# Sheet1.net
KiCad netlist of a schematic drawn in Altium Designer
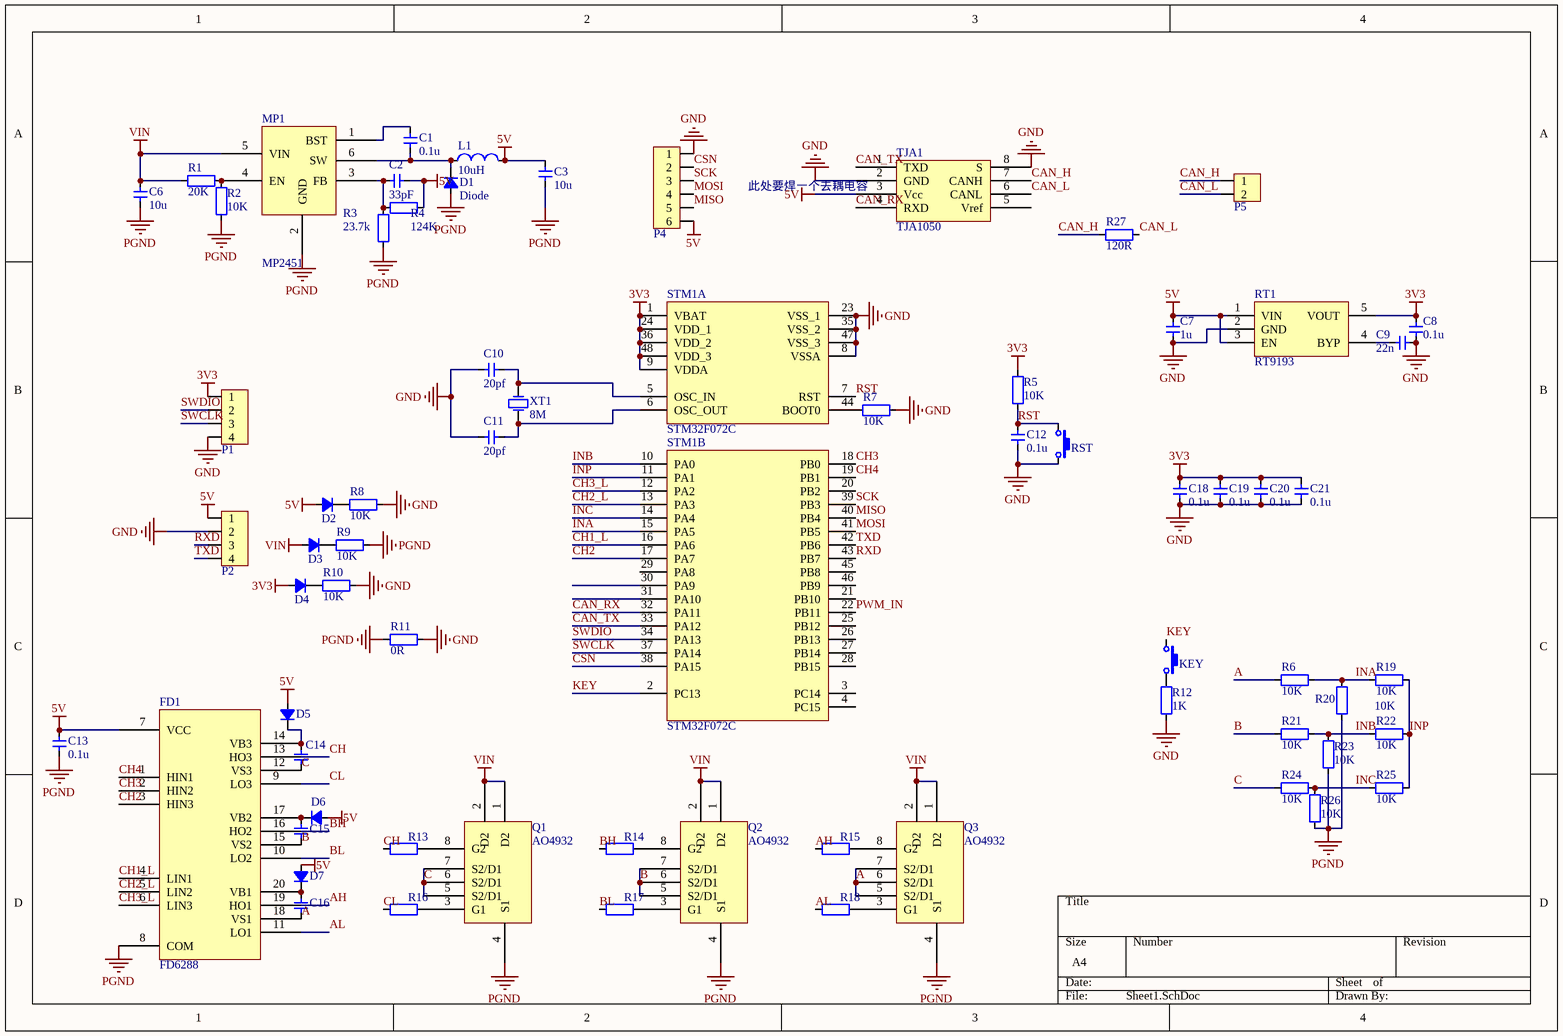
[diagram p0: Sheet1.SchDoc]

(export (version "E")
  (design (tool "Eeschema 10.0.6"))
  (components
    (comp (ref "C1")
      (value "0.1u")
      (footprint "PCB_PassiveCap:CAP_0603")
      (description "Capacitor")
      (fields (field (name "Comment") "Cap_0603"))
      (libsource (lib "SCH_Passive") (part "Cap_0603"))
    )
    (comp (ref "C2")
      (value "33pF")
      (footprint "PCB_PassiveCap:CAP_0603")
      (description "Capacitor")
      (fields (field (name "Comment") "Cap_0603"))
      (libsource (lib "SCH_Passive") (part "Cap_0603"))
    )
    (comp (ref "C3")
      (value "10u")
      (footprint "PCB_PassiveCap:CAP_0805")
      (description "Capacitor")
      (fields (field (name "Comment") "Cap_0805"))
      (libsource (lib "SCH_Passive") (part "Cap_0805"))
    )
    (comp (ref "C6")
      (value "10u")
      (footprint "PCB_PassiveCap:CAP_0805")
      (description "Capacitor")
      (fields (field (name "Comment") "Cap_0805"))
      (libsource (lib "SCH_Passive") (part "Cap_0805"))
    )
    (comp (ref "C7")
      (value "1u")
      (footprint "PCB_PassiveCap:CAP_0603")
      (description "Capacitor")
      (fields (field (name "Comment") "Cap_0603"))
      (libsource (lib "SCH_Passive") (part "Cap_0603"))
    )
    (comp (ref "C8")
      (value "0.1u")
      (footprint "PCB_PassiveCap:CAP_0603")
      (description "Capacitor")
      (fields (field (name "Comment") "Cap_0603"))
      (libsource (lib "SCH_Passive") (part "Cap_0603"))
    )
    (comp (ref "C9")
      (value "22n")
      (footprint "PCB_PassiveCap:CAP_0603")
      (description "Capacitor")
      (fields (field (name "Comment") "Cap_0603"))
      (libsource (lib "SCH_Passive") (part "Cap_0603"))
    )
    (comp (ref "C10")
      (value "20pf")
      (footprint "PCB_PassiveCap:CAP_0603")
      (description "Capacitor")
      (fields (field (name "Comment") "Cap_0603"))
      (libsource (lib "SCH_Passive") (part "Cap_0603"))
    )
    (comp (ref "C11")
      (value "20pf")
      (footprint "PCB_PassiveCap:CAP_0603")
      (description "Capacitor")
      (fields (field (name "Comment") "Cap_0603"))
      (libsource (lib "SCH_Passive") (part "Cap_0603"))
    )
    (comp (ref "C12")
      (value "0.1u")
      (footprint "PCB_PassiveCap:CAP_0603")
      (description "Capacitor")
      (fields (field (name "Comment") "Cap_0603"))
      (libsource (lib "SCH_Passive") (part "Cap_0603"))
    )
    (comp (ref "C13")
      (value "0.1u")
      (footprint "PCB_PassiveCap:CAP_0603")
      (description "Capacitor")
      (fields (field (name "Comment") "Cap_0603"))
      (libsource (lib "SCH_Passive") (part "Cap_0603"))
    )
    (comp (ref "C14")
      (value "Cap_0603")
      (footprint "PCB_PassiveCap:CAP_0603")
      (description "Capacitor")
      (libsource (lib "SCH_Passive") (part "Cap_0603"))
    )
    (comp (ref "C15")
      (value "Cap_0603")
      (footprint "PCB_PassiveCap:CAP_0603")
      (description "Capacitor")
      (libsource (lib "SCH_Passive") (part "Cap_0603"))
    )
    (comp (ref "C16")
      (value "Cap_0603")
      (footprint "PCB_PassiveCap:CAP_0603")
      (description "Capacitor")
      (libsource (lib "SCH_Passive") (part "Cap_0603"))
    )
    (comp (ref "C18")
      (value "0.1u")
      (footprint "PCB_PassiveCap:CAP_0603")
      (description "Capacitor")
      (fields (field (name "Comment") "Cap_0603"))
      (libsource (lib "SCH_Passive") (part "Cap_0603"))
    )
    (comp (ref "C19")
      (value "0.1u")
      (footprint "PCB_PassiveCap:CAP_0603")
      (description "Capacitor")
      (fields (field (name "Comment") "Cap_0603"))
      (libsource (lib "SCH_Passive") (part "Cap_0603"))
    )
    (comp (ref "C20")
      (value "0.1u")
      (footprint "PCB_PassiveCap:CAP_0603")
      (description "Capacitor")
      (fields (field (name "Comment") "Cap_0603"))
      (libsource (lib "SCH_Passive") (part "Cap_0603"))
    )
    (comp (ref "C21")
      (value "0.1u")
      (footprint "PCB_PassiveCap:CAP_0603")
      (description "Capacitor")
      (fields (field (name "Comment") "Cap_0603"))
      (libsource (lib "SCH_Passive") (part "Cap_0603"))
    )
    (comp (ref "D1") (value "Diode") (footprint "LED_0805_RED") (libsource (lib "SCH_Active") (part "Diode")))
    (comp (ref "D2")
      (value "D_0805")
      (footprint "LED_0805_YELLOW")
      (libsource (lib "SCH_Active") (part "D_0805"))
    )
    (comp (ref "D3")
      (value "D_0805")
      (footprint "LED_0805_YELLOW")
      (libsource (lib "SCH_Active") (part "D_0805"))
    )
    (comp (ref "D4")
      (value "D_0805")
      (footprint "LED_0805_YELLOW")
      (libsource (lib "SCH_Active") (part "D_0805"))
    )
    (comp (ref "D5")
      (value "D_0805")
      (footprint "LED_0805_YELLOW")
      (libsource (lib "SCH_Active") (part "D_0805"))
    )
    (comp (ref "D6")
      (value "D_0805")
      (footprint "LED_0805_YELLOW")
      (libsource (lib "SCH_Active") (part "D_0805"))
    )
    (comp (ref "D7")
      (value "D_0805")
      (footprint "LED_0805_YELLOW")
      (libsource (lib "SCH_Active") (part "D_0805"))
    )
    (comp (ref "FD1")
      (value "FD6288")
      (footprint "TSSOP_E170_P0.65_20")
      (libsource (lib "SCH_IntegratedCircuit") (part "FD6288"))
    )
    (comp (ref "KEY")
      (value "ButtonTACT_3x4x2_180")
      (footprint "PCB_Switch:ButtonTACT_3x4x2_180H")
      (description "Button")
      (libsource (lib "SCH_Switch") (part "ButtonTACT_3x4x2_180"))
    )
    (comp (ref "L1")
      (value "10uH")
      (footprint "IND_CD52")
      (description "Inductor")
      (fields (field (name "Comment") "Ind_CD32"))
      (libsource (lib "SCH_Passive") (part "Ind_CD32"))
    )
    (comp (ref "MP1")
      (value "MP2451")
      (footprint "SOT23-6")
      (libsource (lib "SCH_IntegratedCircuit") (part "MP2451"))
    )
    (comp (ref "P1")
      (value "HDR1x4_2.54")
      (footprint "PCB_ConnectorHDR:HDR1x4_2.54_180")
      (description "Header")
      (libsource (lib "SCH_ConnectorHDR") (part "HDR1x4_2.54"))
    )
    (comp (ref "P2")
      (value "HDR1x4_2.54")
      (footprint "PCB_ConnectorHDR:HDR1x4_2.54_180")
      (description "Header")
      (libsource (lib "SCH_ConnectorHDR") (part "HDR1x4_2.54"))
    )
    (comp (ref "P4")
      (value "HDR1x6_2.54")
      (footprint "PCB_ConnectorHDR:1.25mm_1X6_SMT")
      (description "Header")
      (libsource (lib "SCH_ConnectorHDR") (part "HDR1x6_2.54T"))
    )
    (comp (ref "P5")
      (value "HDR1x2_2.54")
      (footprint "PCB_ConnectorHDR:HDR1X2_2.54_180")
      (description "Header")
      (libsource (lib "SCH_ConnectorHDR") (part "HDR1x2_2.54"))
    )
    (comp (ref "Q1") (value "AO4932") (footprint "SOP_E150_8") (libsource (lib "SCH_Active") (part "AO4932")))
    (comp (ref "Q2") (value "AO4932") (footprint "SOP_E150_8") (libsource (lib "SCH_Active") (part "AO4932")))
    (comp (ref "Q3") (value "AO4932") (footprint "SOP_E150_8") (libsource (lib "SCH_Active") (part "AO4932")))
    (comp (ref "R1")
      (value "20K")
      (footprint "PCB_PassiveRes:RES_0603")
      (description "Resistor")
      (fields (field (name "Comment") "Res_0603"))
      (libsource (lib "") (part "Res_0603_1"))
    )
    (comp (ref "R2")
      (value "10K")
      (footprint "PCB_PassiveRes:RES_0603")
      (description "Resistor")
      (fields (field (name "Comment") "Res_0603"))
      (libsource (lib "") (part "Res_0603_3"))
    )
    (comp (ref "R3")
      (value "23.7k")
      (footprint "PCB_PassiveRes:RES_0603")
      (description "Resistor")
      (fields (field (name "Comment") "Res_0603"))
      (libsource (lib "") (part "Res_0603_3"))
    )
    (comp (ref "R4")
      (value "124K")
      (footprint "PCB_PassiveRes:RES_0603")
      (description "Resistor")
      (fields (field (name "Comment") "Res_0603"))
      (libsource (lib "") (part "Res_0603_1"))
    )
    (comp (ref "R5")
      (value "10K")
      (footprint "PCB_PassiveRes:RES_0603")
      (description "Resistor")
      (fields (field (name "Comment") "Res_0603"))
      (libsource (lib "SCH_Passive") (part "Res_0603"))
    )
    (comp (ref "R6")
      (value "10K")
      (footprint "PCB_PassiveRes:RES_0603")
      (description "Resistor")
      (fields (field (name "Comment") "Res_0603"))
      (libsource (lib "") (part "Res_0603_1"))
    )
    (comp (ref "R7")
      (value "10K")
      (footprint "PCB_PassiveRes:RES_0603")
      (description "Resistor")
      (fields (field (name "Comment") "Res_0603"))
      (libsource (lib "") (part "Res_0603_2"))
    )
    (comp (ref "R8")
      (value "10K")
      (footprint "PCB_PassiveRes:RES_0603")
      (description "Resistor")
      (fields (field (name "Comment") "Res_0603"))
      (libsource (lib "") (part "Res_0603_1"))
    )
    (comp (ref "R9")
      (value "10K")
      (footprint "PCB_PassiveRes:RES_0603")
      (description "Resistor")
      (fields (field (name "Comment") "Res_0603"))
      (libsource (lib "") (part "Res_0603_1"))
    )
    (comp (ref "R10")
      (value "10K")
      (footprint "PCB_PassiveRes:RES_0603")
      (description "Resistor")
      (fields (field (name "Comment") "Res_0603"))
      (libsource (lib "") (part "Res_0603_1"))
    )
    (comp (ref "R11")
      (value "0R")
      (footprint "PCB_PassiveRes:RES_0603")
      (description "Resistor")
      (fields (field (name "Comment") "Res_0603"))
      (libsource (lib "") (part "Res_0603_1"))
    )
    (comp (ref "R12")
      (value "1K")
      (footprint "PCB_PassiveRes:RES_0603")
      (description "Resistor")
      (fields (field (name "Comment") "Res_0603"))
      (libsource (lib "SCH_Passive") (part "Res_0603"))
    )
    (comp (ref "R13")
      (value "Res_0603")
      (footprint "PCB_PassiveRes:RES_0603")
      (description "Resistor")
      (libsource (lib "") (part "Res_0603_1"))
    )
    (comp (ref "R14")
      (value "Res_0603")
      (footprint "PCB_PassiveRes:RES_0603")
      (description "Resistor")
      (libsource (lib "") (part "Res_0603_1"))
    )
    (comp (ref "R15")
      (value "Res_0603")
      (footprint "PCB_PassiveRes:RES_0603")
      (description "Resistor")
      (libsource (lib "") (part "Res_0603_1"))
    )
    (comp (ref "R16")
      (value "Res_0603")
      (footprint "PCB_PassiveRes:RES_0603")
      (description "Resistor")
      (libsource (lib "") (part "Res_0603_1"))
    )
    (comp (ref "R17")
      (value "Res_0603")
      (footprint "PCB_PassiveRes:RES_0603")
      (description "Resistor")
      (libsource (lib "") (part "Res_0603_1"))
    )
    (comp (ref "R18")
      (value "Res_0603")
      (footprint "PCB_PassiveRes:RES_0603")
      (description "Resistor")
      (libsource (lib "") (part "Res_0603_1"))
    )
    (comp (ref "R19")
      (value "10K")
      (footprint "PCB_PassiveRes:RES_0603")
      (description "Resistor")
      (fields (field (name "Comment") "Res_0603"))
      (libsource (lib "") (part "Res_0603_1"))
    )
    (comp (ref "R20")
      (value "10K")
      (footprint "PCB_PassiveRes:RES_0603")
      (description "Resistor")
      (fields (field (name "Comment") "Res_0603"))
      (libsource (lib "SCH_Passive") (part "Res_0603"))
    )
    (comp (ref "R21")
      (value "10K")
      (footprint "PCB_PassiveRes:RES_0603")
      (description "Resistor")
      (fields (field (name "Comment") "Res_0603"))
      (libsource (lib "") (part "Res_0603_1"))
    )
    (comp (ref "R22")
      (value "10K")
      (footprint "PCB_PassiveRes:RES_0603")
      (description "Resistor")
      (fields (field (name "Comment") "Res_0603"))
      (libsource (lib "") (part "Res_0603_1"))
    )
    (comp (ref "R23")
      (value "10K")
      (footprint "PCB_PassiveRes:RES_0603")
      (description "Resistor")
      (fields (field (name "Comment") "Res_0603"))
      (libsource (lib "SCH_Passive") (part "Res_0603"))
    )
    (comp (ref "R24")
      (value "10K")
      (footprint "PCB_PassiveRes:RES_0603")
      (description "Resistor")
      (fields (field (name "Comment") "Res_0603"))
      (libsource (lib "") (part "Res_0603_1"))
    )
    (comp (ref "R25")
      (value "10K")
      (footprint "PCB_PassiveRes:RES_0603")
      (description "Resistor")
      (fields (field (name "Comment") "Res_0603"))
      (libsource (lib "") (part "Res_0603_1"))
    )
    (comp (ref "R26")
      (value "10K")
      (footprint "PCB_PassiveRes:RES_0603")
      (description "Resistor")
      (fields (field (name "Comment") "Res_0603"))
      (libsource (lib "SCH_Passive") (part "Res_0603"))
    )
    (comp (ref "R27")
      (value "120R")
      (footprint "PCB_PassiveRes:RES_0603")
      (description "Resistor")
      (fields (field (name "Comment") "Res_0603"))
      (libsource (lib "") (part "Res_0603_2"))
    )
    (comp (ref "RST")
      (value "ButtonTACT_3x4x2_180")
      (footprint "PCB_Switch:ButtonTACT_3x4x2_180H")
      (description "Button")
      (libsource (lib "SCH_Switch") (part "ButtonTACT_3x4x2_180"))
    )
    (comp (ref "RT1")
      (value "RT9193")
      (footprint "PCB_IntegratedCircuit:SOT23-5")
      (description "Power")
      (libsource (lib "SCH_IntegratedCircuit") (part "RT9193"))
    )
    (comp (ref "STM1")
      (value "STM32F072C")
      (footprint "PCB_IntegratedCircuit:LQFP_P0.5_48")
      (description "MCU")
      (libsource (lib "SCH_IntegratedCircuit") (part "STM32F103C"))
    )
    (comp (ref "TJA1")
      (value "TJA1050")
      (footprint "SOP_E150_8")
      (libsource (lib "SCH_IntegratedCircuit") (part "TJA1050"))
    )
    (comp (ref "XT1")
      (value "8M")
      (footprint "PCB_Oscillator:XT_5032_2")
      (description "Crystal Oscillator")
      (fields (field (name "Comment") "XTAL_5032_2P"))
      (libsource (lib "SCH_Oscillator") (part "XTAL_5032_2P"))
    )
  )
  (nets
    (net (code "1") (name "/A") (class "Default")
      (node (ref "C16") (pin "2") (pinfunction "2_2") (pintype "passive"))
      (node (ref "FD1") (pin "18") (pinfunction "VS1_18") (pintype "passive"))
      (node (ref "Q3") (pin "5") (pinfunction "S2/D1_5") (pintype "passive"))
      (node (ref "Q3") (pin "6") (pinfunction "S2/D1_6") (pintype "passive"))
      (node (ref "Q3") (pin "7") (pinfunction "S2/D1_7") (pintype "passive"))
      (node (ref "R6") (pin "1") (pinfunction "1_1") (pintype "passive"))
    )
    (net (code "2") (name "/AH") (class "Default")
      (node (ref "FD1") (pin "19") (pinfunction "HO1_19") (pintype "passive"))
      (node (ref "R15") (pin "1") (pinfunction "1_1") (pintype "passive"))
    )
    (net (code "3") (name "/AL") (class "Default")
      (node (ref "FD1") (pin "11") (pinfunction "LO1_11") (pintype "passive"))
      (node (ref "R18") (pin "1") (pinfunction "1_1") (pintype "passive"))
    )
    (net (code "4") (name "/B") (class "Default")
      (node (ref "C15") (pin "2") (pinfunction "2_2") (pintype "passive"))
      (node (ref "FD1") (pin "15") (pinfunction "VS2_15") (pintype "passive"))
      (node (ref "Q2") (pin "5") (pinfunction "S2/D1_5") (pintype "passive"))
      (node (ref "Q2") (pin "6") (pinfunction "S2/D1_6") (pintype "passive"))
      (node (ref "Q2") (pin "7") (pinfunction "S2/D1_7") (pintype "passive"))
      (node (ref "R21") (pin "1") (pinfunction "1_1") (pintype "passive"))
    )
    (net (code "5") (name "/BH") (class "Default")
      (node (ref "FD1") (pin "16") (pinfunction "HO2_16") (pintype "passive"))
      (node (ref "R14") (pin "1") (pinfunction "1_1") (pintype "passive"))
    )
    (net (code "6") (name "/BL") (class "Default")
      (node (ref "FD1") (pin "10") (pinfunction "LO2_10") (pintype "passive"))
      (node (ref "R17") (pin "1") (pinfunction "1_1") (pintype "passive"))
    )
    (net (code "7") (name "/C") (class "Default")
      (node (ref "C14") (pin "2") (pinfunction "2_2") (pintype "passive"))
      (node (ref "FD1") (pin "12") (pinfunction "VS3_12") (pintype "passive"))
      (node (ref "Q1") (pin "5") (pinfunction "S2/D1_5") (pintype "passive"))
      (node (ref "Q1") (pin "6") (pinfunction "S2/D1_6") (pintype "passive"))
      (node (ref "Q1") (pin "7") (pinfunction "S2/D1_7") (pintype "passive"))
      (node (ref "R24") (pin "1") (pinfunction "1_1") (pintype "passive"))
    )
    (net (code "8") (name "/CAN_H") (class "Default")
      (node (ref "P5") (pin "1") (pinfunction "1_1") (pintype "passive"))
      (node (ref "R27") (pin "2") (pinfunction "2_2") (pintype "passive"))
      (node (ref "TJA1") (pin "7") (pinfunction "CANH_7") (pintype "passive"))
    )
    (net (code "9") (name "/CAN_L") (class "Default")
      (node (ref "P5") (pin "2") (pinfunction "2_2") (pintype "passive"))
      (node (ref "R27") (pin "1") (pinfunction "1_1") (pintype "passive"))
      (node (ref "TJA1") (pin "6") (pinfunction "CANL_6") (pintype "passive"))
    )
    (net (code "10") (name "/CAN_RX") (class "Default")
      (node (ref "STM1") (pin "32") (pinfunction "PA11_32") (pintype "passive"))
      (node (ref "TJA1") (pin "4") (pinfunction "RXD_4") (pintype "passive"))
    )
    (net (code "11") (name "/CAN_TX") (class "Default")
      (node (ref "STM1") (pin "33") (pinfunction "PA12_33") (pintype "passive"))
      (node (ref "TJA1") (pin "1") (pinfunction "TXD_1") (pintype "passive"))
    )
    (net (code "12") (name "/CH") (class "Default")
      (node (ref "FD1") (pin "13") (pinfunction "HO3_13") (pintype "passive"))
      (node (ref "R13") (pin "1") (pinfunction "1_1") (pintype "passive"))
    )
    (net (code "13") (name "/CH1_L") (class "Default")
      (node (ref "FD1") (pin "4") (pinfunction "LIN1_4") (pintype "passive"))
      (node (ref "STM1") (pin "16") (pinfunction "PA6_16") (pintype "passive"))
    )
    (net (code "14") (name "/CH2") (class "Default")
      (node (ref "FD1") (pin "3") (pinfunction "HIN3_3") (pintype "passive"))
      (node (ref "STM1") (pin "17") (pinfunction "PA7_17") (pintype "passive"))
    )
    (net (code "15") (name "/CH2_L") (class "Default")
      (node (ref "FD1") (pin "5") (pinfunction "LIN2_5") (pintype "passive"))
      (node (ref "STM1") (pin "13") (pinfunction "PA3_13") (pintype "passive"))
    )
    (net (code "16") (name "/CH3") (class "Default")
      (node (ref "FD1") (pin "2") (pinfunction "HIN2_2") (pintype "passive"))
      (node (ref "STM1") (pin "18") (pinfunction "PB0_18") (pintype "passive"))
    )
    (net (code "17") (name "/CH3_L") (class "Default")
      (node (ref "FD1") (pin "6") (pinfunction "LIN3_6") (pintype "passive"))
      (node (ref "STM1") (pin "12") (pinfunction "PA2_12") (pintype "passive"))
    )
    (net (code "18") (name "/CH4") (class "Default")
      (node (ref "FD1") (pin "1") (pinfunction "HIN1_1") (pintype "passive"))
      (node (ref "STM1") (pin "19") (pinfunction "PB1_19") (pintype "passive"))
    )
    (net (code "19") (name "/CL") (class "Default")
      (node (ref "FD1") (pin "9") (pinfunction "LO3_9") (pintype "passive"))
      (node (ref "R16") (pin "1") (pinfunction "1_1") (pintype "passive"))
    )
    (net (code "20") (name "/CSN") (class "Default")
      (node (ref "P4") (pin "2") (pinfunction "2_2") (pintype "passive"))
      (node (ref "STM1") (pin "38") (pinfunction "PA15_38") (pintype "passive"))
    )
    (net (code "21") (name "/INA") (class "Default")
      (node (ref "R19") (pin "1") (pinfunction "1_1") (pintype "passive"))
      (node (ref "R20") (pin "2") (pinfunction "2_2") (pintype "passive"))
      (node (ref "R6") (pin "2") (pinfunction "2_2") (pintype "passive"))
      (node (ref "STM1") (pin "15") (pinfunction "PA5_15") (pintype "passive"))
    )
    (net (code "22") (name "/INB") (class "Default")
      (node (ref "R21") (pin "2") (pinfunction "2_2") (pintype "passive"))
      (node (ref "R22") (pin "1") (pinfunction "1_1") (pintype "passive"))
      (node (ref "R23") (pin "2") (pinfunction "2_2") (pintype "passive"))
      (node (ref "STM1") (pin "10") (pinfunction "PA0_10") (pintype "passive"))
    )
    (net (code "23") (name "/INC") (class "Default")
      (node (ref "R24") (pin "2") (pinfunction "2_2") (pintype "passive"))
      (node (ref "R25") (pin "1") (pinfunction "1_1") (pintype "passive"))
      (node (ref "R26") (pin "2") (pinfunction "2_2") (pintype "passive"))
      (node (ref "STM1") (pin "14") (pinfunction "PA4_14") (pintype "passive"))
    )
    (net (code "24") (name "/INP") (class "Default")
      (node (ref "R19") (pin "2") (pinfunction "2_2") (pintype "passive"))
      (node (ref "R22") (pin "2") (pinfunction "2_2") (pintype "passive"))
      (node (ref "R25") (pin "2") (pinfunction "2_2") (pintype "passive"))
      (node (ref "STM1") (pin "11") (pinfunction "PA1_11") (pintype "passive"))
    )
    (net (code "25") (name "/KEY") (class "Default")
      (node (ref "KEY") (pin "1") (pinfunction "1_1") (pintype "passive"))
      (node (ref "STM1") (pin "2") (pinfunction "PC13_2") (pintype "passive"))
    )
    (net (code "26") (name "/MISO") (class "Default")
      (node (ref "P4") (pin "5") (pinfunction "5_5") (pintype "passive"))
      (node (ref "STM1") (pin "40") (pinfunction "PB4_40") (pintype "passive"))
    )
    (net (code "27") (name "/MOSI") (class "Default")
      (node (ref "P4") (pin "4") (pinfunction "4_4") (pintype "passive"))
      (node (ref "STM1") (pin "41") (pinfunction "PB5_41") (pintype "passive"))
    )
    (net (code "28") (name "/PWM_IN") (class "Default")
      (node (ref "STM1") (pin "22") (pinfunction "PB11_22") (pintype "passive"))
    )
    (net (code "29") (name "/RST") (class "Default")
      (node (ref "C12") (pin "2") (pinfunction "2_2") (pintype "passive"))
      (node (ref "R5") (pin "1") (pinfunction "1_1") (pintype "passive"))
      (node (ref "RST") (pin "1") (pinfunction "1_1") (pintype "passive"))
      (node (ref "STM1") (pin "7") (pinfunction "RST_7") (pintype "passive"))
    )
    (net (code "30") (name "/RXD") (class "Default")
      (node (ref "P2") (pin "3") (pinfunction "3_3") (pintype "passive"))
      (node (ref "STM1") (pin "43") (pinfunction "PB7_43") (pintype "passive"))
    )
    (net (code "31") (name "/SCK") (class "Default")
      (node (ref "P4") (pin "3") (pinfunction "3_3") (pintype "passive"))
      (node (ref "STM1") (pin "39") (pinfunction "PB3_39") (pintype "passive"))
    )
    (net (code "32") (name "/SWCLK") (class "Default")
      (node (ref "P1") (pin "3") (pinfunction "3_3") (pintype "passive"))
      (node (ref "STM1") (pin "37") (pinfunction "PA14_37") (pintype "passive"))
    )
    (net (code "33") (name "/SWDIO") (class "Default")
      (node (ref "P1") (pin "2") (pinfunction "2_2") (pintype "passive"))
      (node (ref "STM1") (pin "34") (pinfunction "PA13_34") (pintype "passive"))
    )
    (net (code "34") (name "/TXD") (class "Default")
      (node (ref "P2") (pin "4") (pinfunction "4_4") (pintype "passive"))
      (node (ref "STM1") (pin "42") (pinfunction "PB6_42") (pintype "passive"))
    )
    (net (code "35") (name "3V3") (class "Default")
      (node (ref "C18") (pin "2") (pinfunction "2_2") (pintype "passive"))
      (node (ref "C19") (pin "2") (pinfunction "2_2") (pintype "passive"))
      (node (ref "C20") (pin "2") (pinfunction "2_2") (pintype "passive"))
      (node (ref "C21") (pin "2") (pinfunction "2_2") (pintype "passive"))
      (node (ref "C8") (pin "2") (pinfunction "2_2") (pintype "passive"))
      (node (ref "D4") (pin "1") (pinfunction "A_1") (pintype "passive"))
      (node (ref "P1") (pin "1") (pinfunction "1_1") (pintype "passive"))
      (node (ref "R5") (pin "2") (pinfunction "2_2") (pintype "passive"))
      (node (ref "RT1") (pin "5") (pinfunction "VOUT_5") (pintype "passive"))
      (node (ref "STM1") (pin "1") (pinfunction "VBAT_1") (pintype "passive"))
      (node (ref "STM1") (pin "24") (pinfunction "VDD_1_24") (pintype "passive"))
      (node (ref "STM1") (pin "36") (pinfunction "VDD_2_36") (pintype "passive"))
      (node (ref "STM1") (pin "48") (pinfunction "VDD_3_48") (pintype "passive"))
      (node (ref "STM1") (pin "9") (pinfunction "VDDA_9") (pintype "passive"))
    )
    (net (code "36") (name "5V") (class "Default")
      (node (ref "C13") (pin "2") (pinfunction "2_2") (pintype "passive"))
      (node (ref "C2") (pin "1") (pinfunction "1_1") (pintype "passive"))
      (node (ref "C3") (pin "2") (pinfunction "2_2") (pintype "passive"))
      (node (ref "C7") (pin "2") (pinfunction "2_2") (pintype "passive"))
      (node (ref "D2") (pin "1") (pinfunction "A_1") (pintype "passive"))
      (node (ref "D5") (pin "1") (pinfunction "A_1") (pintype "passive"))
      (node (ref "D6") (pin "1") (pinfunction "A_1") (pintype "passive"))
      (node (ref "D7") (pin "1") (pinfunction "A_1") (pintype "passive"))
      (node (ref "FD1") (pin "7") (pinfunction "VCC_7") (pintype "passive"))
      (node (ref "L1") (pin "2") (pinfunction "2_2") (pintype "passive"))
      (node (ref "P2") (pin "1") (pinfunction "1_1") (pintype "passive"))
      (node (ref "P4") (pin "6") (pinfunction "6_6") (pintype "passive"))
      (node (ref "R4") (pin "2") (pinfunction "2_2") (pintype "passive"))
      (node (ref "RT1") (pin "1") (pinfunction "VIN_1") (pintype "passive"))
      (node (ref "RT1") (pin "3") (pinfunction "EN_3") (pintype "power_in"))
      (node (ref "TJA1") (pin "3") (pinfunction "Vcc_3") (pintype "passive"))
    )
    (net (code "37") (name "GND") (class "Default")
      (node (ref "C10") (pin "1") (pinfunction "1_1") (pintype "passive"))
      (node (ref "C11") (pin "1") (pinfunction "1_1") (pintype "passive"))
      (node (ref "C12") (pin "1") (pinfunction "1_1") (pintype "passive"))
      (node (ref "C18") (pin "1") (pinfunction "1_1") (pintype "passive"))
      (node (ref "C19") (pin "1") (pinfunction "1_1") (pintype "passive"))
      (node (ref "C20") (pin "1") (pinfunction "1_1") (pintype "passive"))
      (node (ref "C21") (pin "1") (pinfunction "1_1") (pintype "passive"))
      (node (ref "C7") (pin "1") (pinfunction "1_1") (pintype "passive"))
      (node (ref "C8") (pin "1") (pinfunction "1_1") (pintype "passive"))
      (node (ref "C9") (pin "1") (pinfunction "1_1") (pintype "passive"))
      (node (ref "P1") (pin "4") (pinfunction "4_4") (pintype "passive"))
      (node (ref "P2") (pin "2") (pinfunction "2_2") (pintype "passive"))
      (node (ref "P4") (pin "1") (pinfunction "1_1") (pintype "passive"))
      (node (ref "R10") (pin "2") (pinfunction "2_2") (pintype "passive"))
      (node (ref "R11") (pin "2") (pinfunction "2_2") (pintype "passive"))
      (node (ref "R12") (pin "1") (pinfunction "1_1") (pintype "passive"))
      (node (ref "R7") (pin "1") (pinfunction "1_1") (pintype "passive"))
      (node (ref "R8") (pin "2") (pinfunction "2_2") (pintype "passive"))
      (node (ref "RST") (pin "2") (pinfunction "2_2") (pintype "passive"))
      (node (ref "RT1") (pin "2") (pinfunction "GND_2") (pintype "passive"))
      (node (ref "STM1") (pin "23") (pinfunction "VSS_1_23") (pintype "passive"))
      (node (ref "STM1") (pin "35") (pinfunction "VSS_2_35") (pintype "passive"))
      (node (ref "STM1") (pin "47") (pinfunction "VSS_3_47") (pintype "passive"))
      (node (ref "STM1") (pin "8") (pinfunction "VSSA_8") (pintype "passive"))
      (node (ref "TJA1") (pin "2") (pinfunction "GND_2") (pintype "passive"))
      (node (ref "TJA1") (pin "8") (pinfunction "S_8") (pintype "passive"))
    )
    (net (code "38") (name "Net-(D1-K)") (class "Default")
      (node (ref "C1") (pin "1") (pinfunction "1_1") (pintype "passive"))
      (node (ref "D1") (pin "2") (pinfunction "K_2") (pintype "passive"))
      (node (ref "L1") (pin "1") (pinfunction "1_1") (pintype "passive"))
      (node (ref "MP1") (pin "6") (pinfunction "SW_6") (pintype "passive"))
    )
    (net (code "39") (name "Net-(D2-K)") (class "Default")
      (node (ref "D2") (pin "2") (pinfunction "K_2") (pintype "passive"))
      (node (ref "R8") (pin "1") (pinfunction "1_1") (pintype "passive"))
    )
    (net (code "40") (name "Net-(D3-K)") (class "Default")
      (node (ref "D3") (pin "2") (pinfunction "K_2") (pintype "passive"))
      (node (ref "R9") (pin "1") (pinfunction "1_1") (pintype "passive"))
    )
    (net (code "41") (name "Net-(D4-K)") (class "Default")
      (node (ref "D4") (pin "2") (pinfunction "K_2") (pintype "passive"))
      (node (ref "R10") (pin "1") (pinfunction "1_1") (pintype "passive"))
    )
    (net (code "42") (name "Net-(D5-K)") (class "Default")
      (node (ref "C14") (pin "1") (pinfunction "1_1") (pintype "passive"))
      (node (ref "D5") (pin "2") (pinfunction "K_2") (pintype "passive"))
      (node (ref "FD1") (pin "14") (pinfunction "VB3_14") (pintype "passive"))
    )
    (net (code "43") (name "Net-(D6-K)") (class "Default")
      (node (ref "C15") (pin "1") (pinfunction "1_1") (pintype "passive"))
      (node (ref "D6") (pin "2") (pinfunction "K_2") (pintype "passive"))
      (node (ref "FD1") (pin "17") (pinfunction "VB2_17") (pintype "passive"))
    )
    (net (code "44") (name "Net-(D7-K)") (class "Default")
      (node (ref "C16") (pin "1") (pinfunction "1_1") (pintype "passive"))
      (node (ref "D7") (pin "2") (pinfunction "K_2") (pintype "passive"))
      (node (ref "FD1") (pin "20") (pinfunction "VB1_20") (pintype "passive"))
    )
    (net (code "45") (name "Net-(KEY-Pad2)") (class "Default")
      (node (ref "KEY") (pin "2") (pinfunction "2_2") (pintype "passive"))
      (node (ref "R12") (pin "2") (pinfunction "2_2") (pintype "passive"))
    )
    (net (code "46") (name "Net-(MP1-BST)") (class "Default")
      (node (ref "C1") (pin "2") (pinfunction "2_2") (pintype "passive"))
      (node (ref "MP1") (pin "1") (pinfunction "BST_1") (pintype "passive"))
    )
    (net (code "47") (name "Net-(MP1-EN)") (class "Default")
      (node (ref "MP1") (pin "4") (pinfunction "EN_4") (pintype "passive"))
      (node (ref "R1") (pin "2") (pinfunction "2_2") (pintype "passive"))
      (node (ref "R2") (pin "1") (pinfunction "1_1") (pintype "passive"))
    )
    (net (code "48") (name "Net-(MP1-FB)") (class "Default")
      (node (ref "C2") (pin "2") (pinfunction "2_2") (pintype "passive"))
      (node (ref "MP1") (pin "3") (pinfunction "FB_3") (pintype "passive"))
      (node (ref "R3") (pin "1") (pinfunction "1_1") (pintype "passive"))
      (node (ref "R4") (pin "1") (pinfunction "1_1") (pintype "passive"))
    )
    (net (code "49") (name "Net-(Q1-G1)") (class "Default")
      (node (ref "Q1") (pin "3") (pinfunction "G1_3") (pintype "passive"))
      (node (ref "R16") (pin "2") (pinfunction "2_2") (pintype "passive"))
    )
    (net (code "50") (name "Net-(Q1-G2)") (class "Default")
      (node (ref "Q1") (pin "8") (pinfunction "G2_8") (pintype "passive"))
      (node (ref "R13") (pin "2") (pinfunction "2_2") (pintype "passive"))
    )
    (net (code "51") (name "Net-(Q2-G1)") (class "Default")
      (node (ref "Q2") (pin "3") (pinfunction "G1_3") (pintype "passive"))
      (node (ref "R17") (pin "2") (pinfunction "2_2") (pintype "passive"))
    )
    (net (code "52") (name "Net-(Q2-G2)") (class "Default")
      (node (ref "Q2") (pin "8") (pinfunction "G2_8") (pintype "passive"))
      (node (ref "R14") (pin "2") (pinfunction "2_2") (pintype "passive"))
    )
    (net (code "53") (name "Net-(Q3-G1)") (class "Default")
      (node (ref "Q3") (pin "3") (pinfunction "G1_3") (pintype "passive"))
      (node (ref "R18") (pin "2") (pinfunction "2_2") (pintype "passive"))
    )
    (net (code "54") (name "Net-(Q3-G2)") (class "Default")
      (node (ref "Q3") (pin "8") (pinfunction "G2_8") (pintype "passive"))
      (node (ref "R15") (pin "2") (pinfunction "2_2") (pintype "passive"))
    )
    (net (code "55") (name "Net-(RT1-BYP)") (class "Default")
      (node (ref "C9") (pin "2") (pinfunction "2_2") (pintype "passive"))
      (node (ref "RT1") (pin "4") (pinfunction "BYP_4") (pintype "passive"))
    )
    (net (code "56") (name "Net-(STM1A-BOOT0)") (class "Default")
      (node (ref "R7") (pin "2") (pinfunction "2_2") (pintype "passive"))
      (node (ref "STM1") (pin "44") (pinfunction "BOOT0_44") (pintype "passive"))
    )
    (net (code "57") (name "Net-(STM1A-OSC_IN)") (class "Default")
      (node (ref "C10") (pin "2") (pinfunction "2_2") (pintype "passive"))
      (node (ref "STM1") (pin "5") (pinfunction "OSC_IN_5") (pintype "passive"))
      (node (ref "XT1") (pin "2") (pinfunction "OSC2_2") (pintype "passive"))
    )
    (net (code "58") (name "Net-(STM1A-OSC_OUT)") (class "Default")
      (node (ref "C11") (pin "2") (pinfunction "2_2") (pintype "passive"))
      (node (ref "STM1") (pin "6") (pinfunction "OSC_OUT_6") (pintype "passive"))
      (node (ref "XT1") (pin "1") (pinfunction "OSC1_1") (pintype "passive"))
    )
    (net (code "59") (name "PGND") (class "Default")
      (node (ref "C13") (pin "1") (pinfunction "1_1") (pintype "passive"))
      (node (ref "C3") (pin "1") (pinfunction "1_1") (pintype "passive"))
      (node (ref "C6") (pin "1") (pinfunction "1_1") (pintype "passive"))
      (node (ref "D1") (pin "1") (pinfunction "A_1") (pintype "passive"))
      (node (ref "FD1") (pin "8") (pinfunction "COM_8") (pintype "passive"))
      (node (ref "MP1") (pin "2") (pinfunction "GND_2") (pintype "passive"))
      (node (ref "Q1") (pin "4") (pinfunction "S1_4") (pintype "passive"))
      (node (ref "Q2") (pin "4") (pinfunction "S1_4") (pintype "passive"))
      (node (ref "Q3") (pin "4") (pinfunction "S1_4") (pintype "passive"))
      (node (ref "R11") (pin "1") (pinfunction "1_1") (pintype "passive"))
      (node (ref "R2") (pin "2") (pinfunction "2_2") (pintype "passive"))
      (node (ref "R20") (pin "1") (pinfunction "1_1") (pintype "passive"))
      (node (ref "R23") (pin "1") (pinfunction "1_1") (pintype "passive"))
      (node (ref "R26") (pin "1") (pinfunction "1_1") (pintype "passive"))
      (node (ref "R3") (pin "2") (pinfunction "2_2") (pintype "passive"))
      (node (ref "R9") (pin "2") (pinfunction "2_2") (pintype "passive"))
    )
    (net (code "60") (name "VIN") (class "Default")
      (node (ref "C6") (pin "2") (pinfunction "2_2") (pintype "passive"))
      (node (ref "D3") (pin "1") (pinfunction "A_1") (pintype "passive"))
      (node (ref "MP1") (pin "5") (pinfunction "VIN_5") (pintype "passive"))
      (node (ref "Q1") (pin "1") (pinfunction "D2_1") (pintype "passive"))
      (node (ref "Q1") (pin "2") (pinfunction "D2_2") (pintype "passive"))
      (node (ref "Q2") (pin "1") (pinfunction "D2_1") (pintype "passive"))
      (node (ref "Q2") (pin "2") (pinfunction "D2_2") (pintype "passive"))
      (node (ref "Q3") (pin "1") (pinfunction "D2_1") (pintype "passive"))
      (node (ref "Q3") (pin "2") (pinfunction "D2_2") (pintype "passive"))
      (node (ref "R1") (pin "1") (pinfunction "1_1") (pintype "passive"))
    )
    (net (code "61") (name "unconnected-(STM1B-PA8-Pad29)") (class "Default")
      (node (ref "STM1") (pin "29") (pinfunction "PA8_29") (pintype "passive"))
    )
    (net (code "62") (name "unconnected-(STM1B-PA9-Pad30)") (class "Default")
      (node (ref "STM1") (pin "30") (pinfunction "PA9_30") (pintype "passive"))
    )
    (net (code "63") (name "unconnected-(STM1B-PA10-Pad31)") (class "Default")
      (node (ref "STM1") (pin "31") (pinfunction "PA10_31") (pintype "passive"))
    )
    (net (code "64") (name "unconnected-(STM1B-PB2-Pad20)") (class "Default")
      (node (ref "STM1") (pin "20") (pinfunction "PB2_20") (pintype "passive"))
    )
    (net (code "65") (name "unconnected-(STM1B-PB8-Pad45)") (class "Default")
      (node (ref "STM1") (pin "45") (pinfunction "PB8_45") (pintype "passive"))
    )
    (net (code "66") (name "unconnected-(STM1B-PB9-Pad46)") (class "Default")
      (node (ref "STM1") (pin "46") (pinfunction "PB9_46") (pintype "passive"))
    )
    (net (code "67") (name "unconnected-(STM1B-PB10-Pad21)") (class "Default")
      (node (ref "STM1") (pin "21") (pinfunction "PB10_21") (pintype "passive"))
    )
    (net (code "68") (name "unconnected-(STM1B-PB12-Pad25)") (class "Default")
      (node (ref "STM1") (pin "25") (pinfunction "PB12_25") (pintype "passive"))
    )
    (net (code "69") (name "unconnected-(STM1B-PB13-Pad26)") (class "Default")
      (node (ref "STM1") (pin "26") (pinfunction "PB13_26") (pintype "passive"))
    )
    (net (code "70") (name "unconnected-(STM1B-PB14-Pad27)") (class "Default")
      (node (ref "STM1") (pin "27") (pinfunction "PB14_27") (pintype "passive"))
    )
    (net (code "71") (name "unconnected-(STM1B-PB15-Pad28)") (class "Default")
      (node (ref "STM1") (pin "28") (pinfunction "PB15_28") (pintype "passive"))
    )
    (net (code "72") (name "unconnected-(STM1B-PC14-Pad3)") (class "Default")
      (node (ref "STM1") (pin "3") (pinfunction "PC14_3") (pintype "passive"))
    )
    (net (code "73") (name "unconnected-(STM1B-PC15-Pad4)") (class "Default")
      (node (ref "STM1") (pin "4") (pinfunction "PC15_4") (pintype "passive"))
    )
    (net (code "74") (name "unconnected-(TJA1-Vref-Pad5)") (class "Default")
      (node (ref "TJA1") (pin "5") (pinfunction "Vref_5") (pintype "passive"))
    )
  )
)
